# 43_Flash-SPI_FLASH_Option.net
KiCad netlist of a schematic drawn in Altium Designer
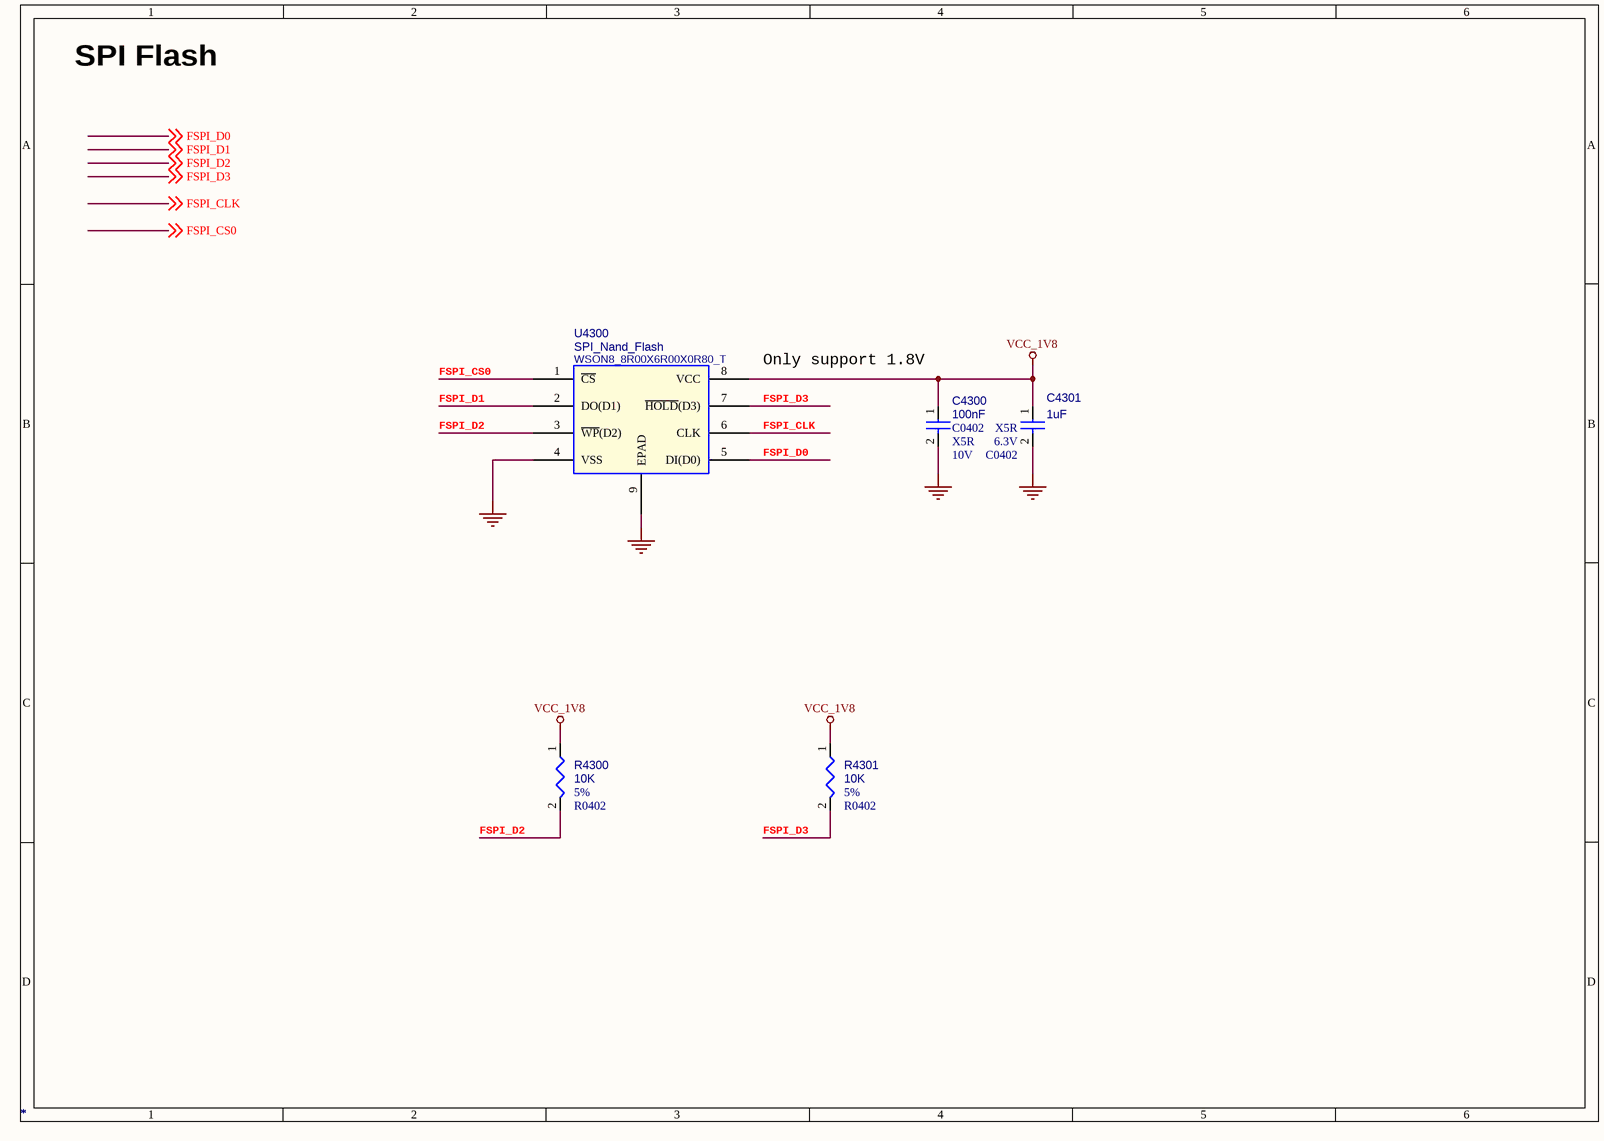
[diagram p0: 43.Flash-SPI FLASH(Option).SchDoc]

(export (version "E")
  (design (tool "Eeschema 10.0.6"))
  (components
    (comp (ref "C4300")
      (value "*")
      (footprint "C0402")
      (description "cap,100.00nF,+/-10%,10V,X5R,C0402")
      (fields
        (field (name "VOLTAGE") "10V")
        (field (name "PCB FOOTPRINT") "C0402")
        (field (name "DIELECTRIC") "X5R")
        (field (name "TOLERANCE") "10%")
        (field (name "MANUFACTURER") "TDK")
        (field (name "ALTIUM_UNNAMED_1") "100nF")
        (field (name "CREATED BY") "JJJ")
      )
      (libsource (lib "*") (part "CAP NP"))
    )
    (comp (ref "C4301")
      (value "*")
      (footprint "C0402")
      (description "cap,1.00uF,+/-10%,6.3V,X5R,C0402")
      (fields
        (field (name "VOLTAGE") "6.3V")
        (field (name "PCB FOOTPRINT") "C0402")
        (field (name "DIELECTRIC") "X5R")
        (field (name "TOLERANCE") "10%")
        (field (name "MANUFACTURER") "TDK")
        (field (name "ALTIUM_UNNAMED_1") "1uF")
        (field (name "CREATED BY") "JJJ")
      )
      (libsource (lib "*") (part "CAP NP"))
    )
    (comp (ref "R4300")
      (value "*")
      (footprint "R0402")
      (description "НЁУГєсД¤µзЧи,10K,+/-5%,R0402,1/16W.")
      (fields
        (field (name "PCB FOOTPRINT") "R0402")
        (field (name "TOLERANCE") "5%")
        (field (name "MANUFACTURER") "YAGEO")
        (field (name "ALTIUM_UNNAMED_1") "10K")
        (field (name "CREATED BY") "YTL")
      )
      (libsource (lib "*") (part "RESISTOR_Dup1"))
    )
    (comp (ref "R4301")
      (value "*")
      (footprint "R0402")
      (description "НЁУГєсД¤µзЧи,10K,+/-5%,R0402,1/16W.")
      (fields
        (field (name "PCB FOOTPRINT") "R0402")
        (field (name "TOLERANCE") "5%")
        (field (name "MANUFACTURER") "YAGEO")
        (field (name "ALTIUM_UNNAMED_1") "10K")
        (field (name "CREATED BY") "YTL")
      )
      (libsource (lib "*") (part "RESISTOR_Dup1"))
    )
    (comp (ref "U4300")
      (value "*")
      (footprint "WSON8_8R00X6R00X0R80_T")
      (fields
        (field (name "PCB FOOTPRINT") "WSON8_8R00X6R00X0R80_T")
        (field (name "ALTIUM_UNNAMED_1") "SPI_Nand_Flash")
        (field (name "CREATED BY") "JJJ")
      )
      (libsource (lib "*") (part "SPI_FLASH_8PIN_T_0"))
    )
  )
  (nets
    (net (code "1") (name "FSPI_CLK") (class "Default")
      (node (ref "U4300") (pin "6") (pinfunction "CLK_6") (pintype "passive"))
    )
    (net (code "2") (name "FSPI_CS0") (class "Default")
      (node (ref "U4300") (pin "1") (pinfunction "~{CS}_1") (pintype "passive"))
    )
    (net (code "3") (name "FSPI_D0") (class "Default")
      (node (ref "U4300") (pin "5") (pinfunction "DI(D0)_5") (pintype "passive"))
    )
    (net (code "4") (name "FSPI_D1") (class "Default")
      (node (ref "U4300") (pin "2") (pinfunction "DO(D1)_2") (pintype "passive"))
    )
    (net (code "5") (name "FSPI_D2") (class "Default")
      (node (ref "R4300") (pin "2") (pinfunction "2_2") (pintype "passive"))
      (node (ref "U4300") (pin "3") (pinfunction "~{WP}(D2)_3") (pintype "passive"))
    )
    (net (code "6") (name "FSPI_D3") (class "Default")
      (node (ref "R4301") (pin "2") (pinfunction "2_2") (pintype "passive"))
      (node (ref "U4300") (pin "7") (pinfunction "~{HOLD}(D3)_7") (pintype "passive"))
    )
    (net (code "7") (name "GND") (class "Default")
      (node (ref "C4300") (pin "2") (pinfunction "2_2") (pintype "passive"))
      (node (ref "C4301") (pin "2") (pinfunction "2_2") (pintype "passive"))
      (node (ref "U4300") (pin "4") (pinfunction "VSS_4") (pintype "passive"))
      (node (ref "U4300") (pin "9") (pinfunction "EPAD_9") (pintype "passive"))
    )
    (net (code "8") (name "VCC_1V8") (class "Default")
      (node (ref "C4300") (pin "1") (pinfunction "1_1") (pintype "passive"))
      (node (ref "C4301") (pin "1") (pinfunction "1_1") (pintype "passive"))
      (node (ref "R4300") (pin "1") (pinfunction "1_1") (pintype "passive"))
      (node (ref "R4301") (pin "1") (pinfunction "1_1") (pintype "passive"))
      (node (ref "U4300") (pin "8") (pinfunction "VCC_8") (pintype "passive"))
    )
  )
)
